# lcd_duffle_pth_mk_3.net
KiCad netlist of a schematic drawn in EAGLE
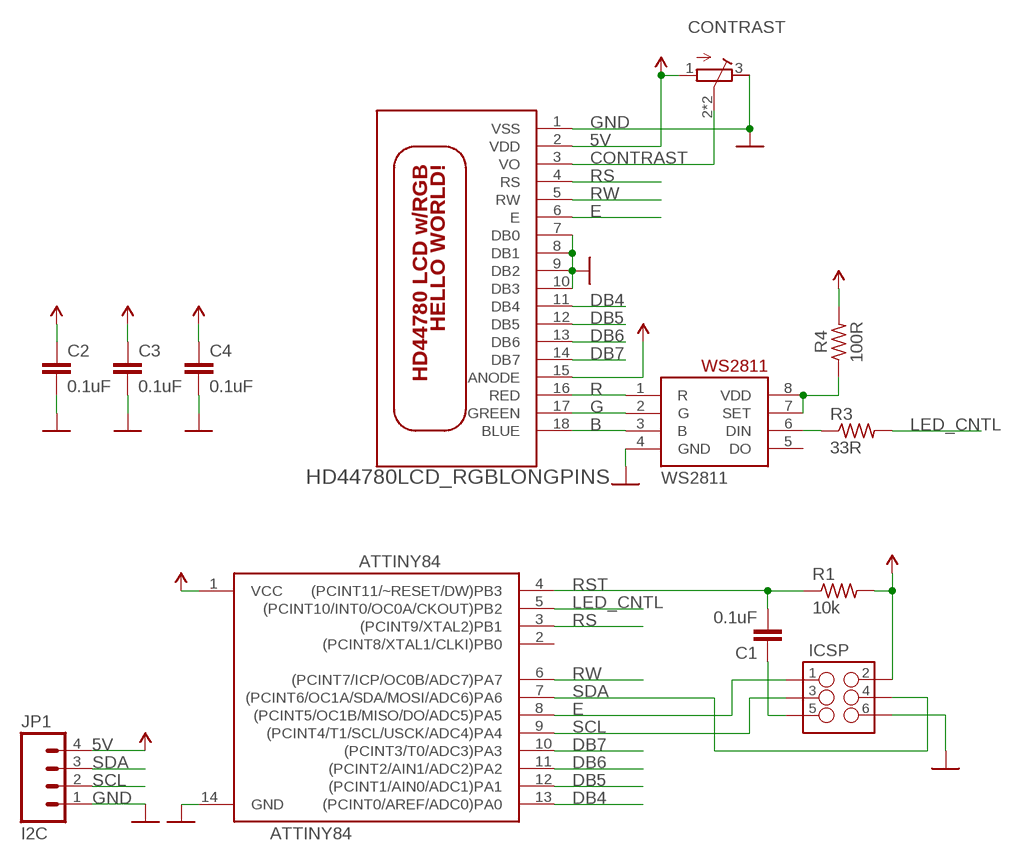
[diagram p0: schematic, sheet 1]

(export (version "E")
  (design (tool "Eeschema 10.0.6"))
  (components
    (comp (ref "ATTINY84")
      (value "ATTINY84")
      (footprint "eagle-import:SO14")
      (libsource (lib "eagle-import") (part "ATTINY84"))
    )
    (comp (ref "C1")
      (value "0.1uF")
      (footprint "eagle-import:C025-024X044")
      (libsource (lib "eagle-import") (part "CAPACITOR-CERAMIC025-024X044"))
    )
    (comp (ref "C2")
      (value "0.1uF")
      (footprint "eagle-import:C025-024X044")
      (libsource (lib "eagle-import") (part "CAPACITOR-CERAMIC025-024X044"))
    )
    (comp (ref "C3")
      (value "0.1uF")
      (footprint "eagle-import:C025-024X044")
      (libsource (lib "eagle-import") (part "CAPACITOR-CERAMIC025-024X044"))
    )
    (comp (ref "C4")
      (value "0.1uF")
      (footprint "eagle-import:C025-024X044")
      (libsource (lib "eagle-import") (part "CAPACITOR-CERAMIC025-024X044"))
    )
    (comp (ref "CONTRAST")
      (value "POTENTIOMETERTHUMBWHEEL-16MM")
      (footprint "eagle-import:POT-THUMBWHEEL")
      (libsource (lib "eagle-import") (part "POTENTIOMETERTHUMBWHEEL-16MM"))
    )
    (comp (ref "ICSP")
      (value "M03X2POGO_PINS")
      (footprint "eagle-import:2X3_POGO")
      (libsource (lib "eagle-import") (part "M03X2POGO_PINS"))
    )
    (comp (ref "JP1")
      (value "I2C")
      (footprint "eagle-import:1X04-2.5MM_JST_XH_RA")
      (libsource (lib "eagle-import") (part "M04-2.5MM_JST_XH_RA"))
    )
    (comp (ref "R1")
      (value "10k")
      (footprint "eagle-import:RESISTOR-AXIAL-PTH-5.08MM")
      (libsource (lib "eagle-import") (part "RESISTORPTH-AXIAL-5.08MM"))
    )
    (comp (ref "R3")
      (value "33R")
      (footprint "eagle-import:RESISTOR-AXIAL-PTH-5.08MM")
      (libsource (lib "eagle-import") (part "RESISTORPTH-AXIAL-5.08MM"))
    )
    (comp (ref "R4")
      (value "100R")
      (footprint "eagle-import:RESISTOR-AXIAL-PTH-5.08MM")
      (libsource (lib "eagle-import") (part "RESISTORPTH-AXIAL-5.08MM"))
    )
    (comp (ref "U$1")
      (value "HD44780LCD_RGBLONGPINS")
      (footprint "eagle-import:LCD1602-RGB-CENTERED")
      (libsource (lib "eagle-import") (part "HD44780LCD_RGBLONGPINS"))
    )
    (comp (ref "WS2811")
      (value "WS2811-SOP8")
      (footprint "eagle-import:SO08-SKINNYPADS")
      (libsource (lib "eagle-import") (part "WS2811-SOP8"))
    )
  )
  (nets
    (net (code "1") (name "/B") (class "Default")
      (node (ref "U$1") (pin "18") (pinfunction "BLUE_18") (pintype "input"))
      (node (ref "WS2811") (pin "3") (pinfunction "B_3") (pintype "open_collector"))
    )
    (net (code "2") (name "/CONTRAST") (class "Default")
      (node (ref "CONTRAST") (pin "2") (pinfunction "S_2") (pintype "passive"))
      (node (ref "CONTRAST") (pin "2@1") (pinfunction "S_2@1") (pintype "passive"))
      (node (ref "U$1") (pin "3") (pinfunction "VO_3") (pintype "input"))
    )
    (net (code "3") (name "/DB4") (class "Default")
      (node (ref "ATTINY84") (pin "13") (pinfunction "(PCINT0/AREF/ADC0)PA0_13") (pintype "bidirectional"))
      (node (ref "U$1") (pin "11") (pinfunction "DB4_11") (pintype "bidirectional"))
    )
    (net (code "4") (name "/DB5") (class "Default")
      (node (ref "ATTINY84") (pin "12") (pinfunction "(PCINT1/AIN0/ADC1)PA1_12") (pintype "bidirectional"))
      (node (ref "U$1") (pin "12") (pinfunction "DB5_12") (pintype "bidirectional"))
    )
    (net (code "5") (name "/DB6") (class "Default")
      (node (ref "ATTINY84") (pin "11") (pinfunction "(PCINT2/AIN1/ADC2)PA2_11") (pintype "bidirectional"))
      (node (ref "U$1") (pin "13") (pinfunction "DB6_13") (pintype "bidirectional"))
    )
    (net (code "6") (name "/DB7") (class "Default")
      (node (ref "ATTINY84") (pin "10") (pinfunction "(PCINT3/T0/ADC3)PA3_10") (pintype "bidirectional"))
      (node (ref "U$1") (pin "14") (pinfunction "DB7_14") (pintype "bidirectional"))
    )
    (net (code "7") (name "/E") (class "Default")
      (node (ref "ATTINY84") (pin "8") (pinfunction "(PCINT5/OC1B/MISO/DO/ADC5)PA5_8") (pintype "bidirectional"))
      (node (ref "ICSP") (pin "P$1") (pinfunction "1_P$1") (pintype "bidirectional"))
      (node (ref "U$1") (pin "6") (pinfunction "E_6") (pintype "input"))
    )
    (net (code "8") (name "/G") (class "Default")
      (node (ref "U$1") (pin "17") (pinfunction "GREEN_17") (pintype "input"))
      (node (ref "WS2811") (pin "2") (pinfunction "G_2") (pintype "open_collector"))
    )
    (net (code "9") (name "/LED_CNTL") (class "Default")
      (node (ref "ATTINY84") (pin "5") (pinfunction "(PCINT10/INT0/OC0A/CKOUT)PB2_5") (pintype "bidirectional"))
      (node (ref "R3") (pin "P$2") (pinfunction "2_P$2") (pintype "passive"))
    )
    (net (code "10") (name "/R") (class "Default")
      (node (ref "U$1") (pin "16") (pinfunction "RED_16") (pintype "input"))
      (node (ref "WS2811") (pin "1") (pinfunction "R_1") (pintype "open_collector"))
    )
    (net (code "11") (name "/RS") (class "Default")
      (node (ref "ATTINY84") (pin "3") (pinfunction "(PCINT9/XTAL2)PB1_3") (pintype "bidirectional"))
      (node (ref "U$1") (pin "4") (pinfunction "RS_4") (pintype "input"))
    )
    (net (code "12") (name "/RST") (class "Default")
      (node (ref "ATTINY84") (pin "4") (pinfunction "(PCINT11/~{RESET/DW})PB3_4") (pintype "bidirectional"))
      (node (ref "C1") (pin "2") (pinfunction "2_2") (pintype "passive"))
      (node (ref "R1") (pin "P$1") (pinfunction "1_P$1") (pintype "passive"))
    )
    (net (code "13") (name "/RW") (class "Default")
      (node (ref "ATTINY84") (pin "6") (pinfunction "(PCINT7/ICP/OC0B/ADC7)PA7_6") (pintype "bidirectional"))
      (node (ref "U$1") (pin "5") (pinfunction "RW_5") (pintype "input"))
    )
    (net (code "14") (name "/SCL") (class "Default")
      (node (ref "ATTINY84") (pin "9") (pinfunction "(PCINT4/T1/SCL/USCK/ADC4)PA4_9") (pintype "bidirectional"))
      (node (ref "ICSP") (pin "P$3") (pinfunction "3_P$3") (pintype "bidirectional"))
      (node (ref "JP1") (pin "2") (pinfunction "2_2") (pintype "passive"))
    )
    (net (code "15") (name "/SDA") (class "Default")
      (node (ref "ATTINY84") (pin "7") (pinfunction "(PCINT6/OC1A/SDA/MOSI/ADC6)PA6_7") (pintype "bidirectional"))
      (node (ref "ICSP") (pin "P$4") (pinfunction "4_P$4") (pintype "bidirectional"))
      (node (ref "JP1") (pin "3") (pinfunction "3_3") (pintype "passive"))
    )
    (net (code "16") (name "5V") (class "Default")
      (node (ref "ATTINY84") (pin "1") (pinfunction "VCC_1") (pintype "bidirectional"))
      (node (ref "C2") (pin "2") (pinfunction "2_2") (pintype "passive"))
      (node (ref "C3") (pin "2") (pinfunction "2_2") (pintype "passive"))
      (node (ref "C4") (pin "2") (pinfunction "2_2") (pintype "passive"))
      (node (ref "CONTRAST") (pin "1") (pinfunction "A_1") (pintype "passive"))
      (node (ref "ICSP") (pin "P$2") (pinfunction "2_P$2") (pintype "bidirectional"))
      (node (ref "JP1") (pin "4") (pinfunction "4_4") (pintype "passive"))
      (node (ref "R1") (pin "P$2") (pinfunction "2_P$2") (pintype "passive"))
      (node (ref "R4") (pin "P$2") (pinfunction "2_P$2") (pintype "passive"))
      (node (ref "U$1") (pin "15") (pinfunction "ANODE_15") (pintype "input"))
      (node (ref "U$1") (pin "2") (pinfunction "VDD_2") (pintype "power_in"))
    )
    (net (code "17") (name "GND") (class "Default")
      (node (ref "ATTINY84") (pin "14") (pinfunction "GND_14") (pintype "bidirectional"))
      (node (ref "C2") (pin "1") (pinfunction "1_1") (pintype "passive"))
      (node (ref "C3") (pin "1") (pinfunction "1_1") (pintype "passive"))
      (node (ref "C4") (pin "1") (pinfunction "1_1") (pintype "passive"))
      (node (ref "CONTRAST") (pin "3") (pinfunction "E_3") (pintype "passive"))
      (node (ref "ICSP") (pin "P$6") (pinfunction "6_P$6") (pintype "bidirectional"))
      (node (ref "JP1") (pin "1") (pinfunction "1_1") (pintype "passive"))
      (node (ref "U$1") (pin "1") (pinfunction "VSS_1") (pintype "power_in"))
      (node (ref "U$1") (pin "10") (pinfunction "DB3_10") (pintype "bidirectional"))
      (node (ref "U$1") (pin "7") (pinfunction "DB0_7") (pintype "bidirectional"))
      (node (ref "U$1") (pin "8") (pinfunction "DB1_8") (pintype "bidirectional"))
      (node (ref "U$1") (pin "9") (pinfunction "DB2_9") (pintype "bidirectional"))
      (node (ref "WS2811") (pin "4") (pinfunction "GND_4") (pintype "power_in"))
    )
    (net (code "18") (name "Net-(ICSP-5)") (class "Default")
      (node (ref "C1") (pin "1") (pinfunction "1_1") (pintype "passive"))
      (node (ref "ICSP") (pin "P$5") (pinfunction "5_P$5") (pintype "bidirectional"))
    )
    (net (code "19") (name "Net-(R3-1)") (class "Default")
      (node (ref "R3") (pin "P$1") (pinfunction "1_P$1") (pintype "passive"))
      (node (ref "WS2811") (pin "6") (pinfunction "DIN_6") (pintype "input"))
    )
    (net (code "20") (name "Net-(R4-1)") (class "Default")
      (node (ref "R4") (pin "P$1") (pinfunction "1_P$1") (pintype "passive"))
      (node (ref "WS2811") (pin "7") (pinfunction "SET_7") (pintype "input"))
      (node (ref "WS2811") (pin "8") (pinfunction "VDD_8") (pintype "power_in"))
    )
    (net (code "21") (name "unconnected-(ATTINY84-(PCINT8{slash}XTAL1{slash}CLKI)PB0-Pad2)") (class "Default")
      (node (ref "ATTINY84") (pin "2") (pinfunction "(PCINT8/XTAL1/CLKI)PB0_2") (pintype "bidirectional"))
    )
    (net (code "22") (name "unconnected-(WS2811-DO-Pad5)") (class "Default")
      (node (ref "WS2811") (pin "5") (pinfunction "DO_5") (pintype "output"))
    )
  )
)
